# TempSensor.net
KiCad netlist of a schematic drawn in Altium Designer
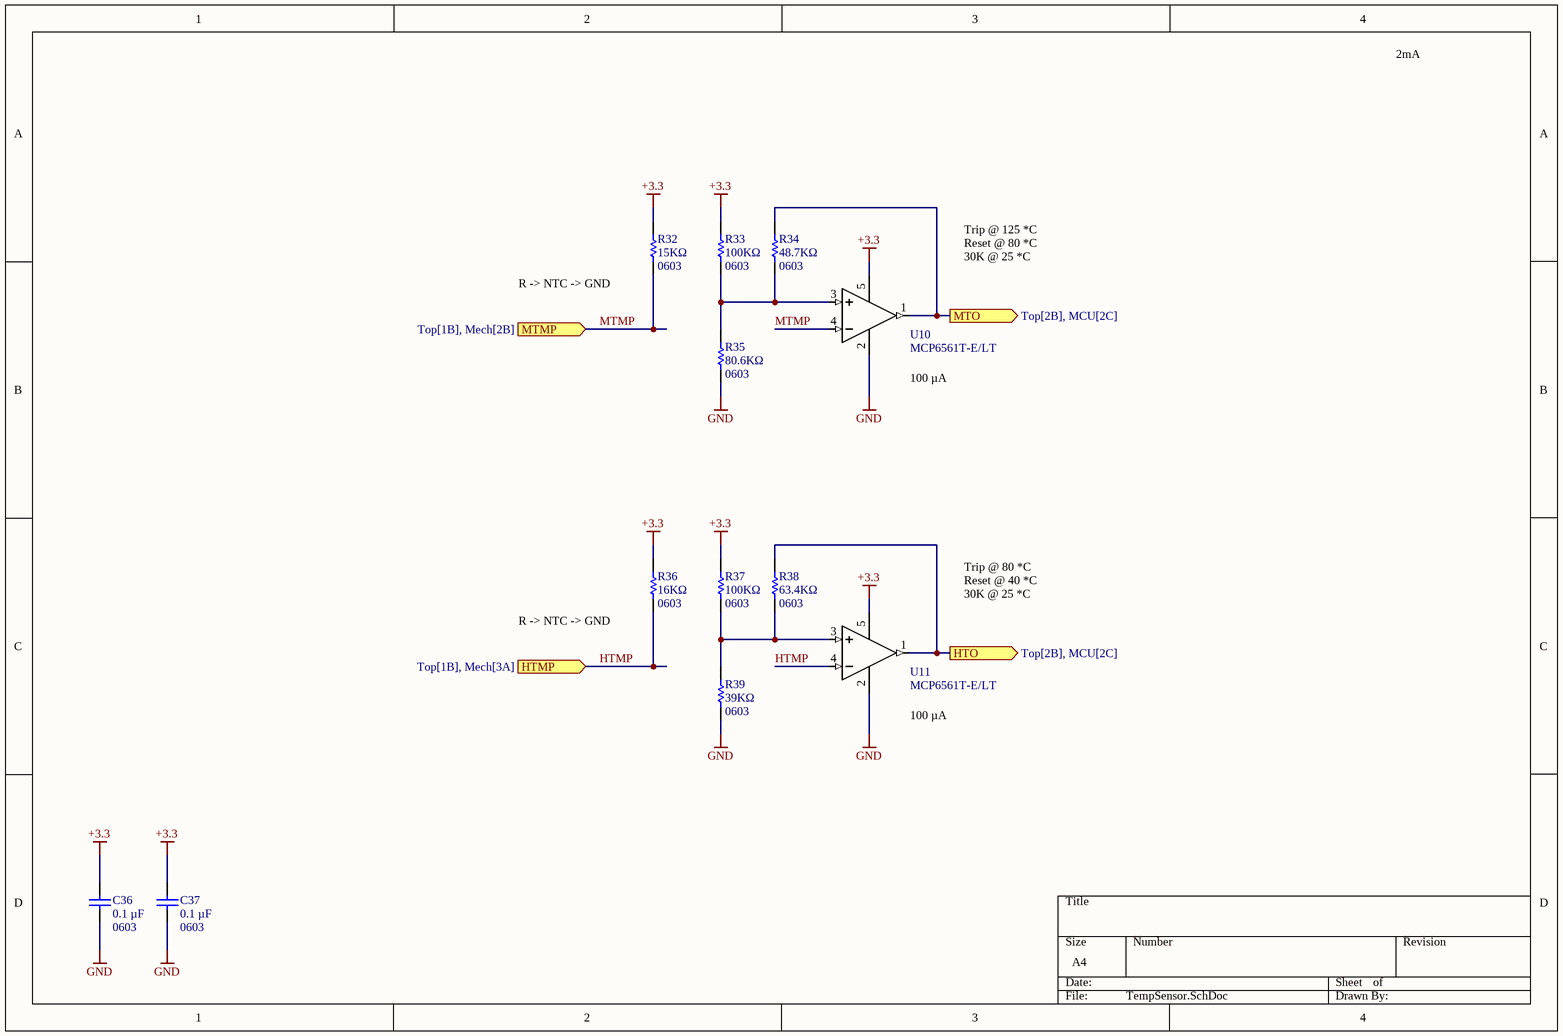
[diagram p0: TempSensor.SchDoc]

(export (version "E")
  (design (tool "Eeschema 10.0.6"))
  (components
    (comp (ref "C36")
      (value "0.1 µF")
      (footprint "0603")
      (description "0.1 µF ±20% 100V Ceramic Capacitor X7R 0603 (1608 Metric)")
      (fields (field (name "CASE") "0603") (field (name "TOLERANCE") "±20%") (field (name "VOLTAGE") "100V"))
      (libsource (lib "Murata Electronics") (part "GRM188R72A104MA35J"))
    )
    (comp (ref "C37")
      (value "0.1 µF")
      (footprint "0603")
      (description "0.1 µF ±20% 100V Ceramic Capacitor X7R 0603 (1608 Metric)")
      (fields (field (name "CASE") "0603") (field (name "TOLERANCE") "±20%") (field (name "VOLTAGE") "100V"))
      (libsource (lib "Murata Electronics") (part "GRM188R72A104MA35J"))
    )
    (comp (ref "R32")
      (value "15KΩ")
      (footprint "0603")
      (description "15 kOhms ±1% 0.1W, 1/10W Chip Resistor 0603 (1608 Metric) Automotive AEC-Q200 Thick Film")
      (fields (field (name "CASE") "0603") (field (name "TOLERANCE") "1%") (field (name "POWER") "0.1W"))
      (libsource (lib "Stackpole Electronics Inc") (part "RMCF0603FG15K0"))
    )
    (comp (ref "R33")
      (value "100KΩ")
      (footprint "0603")
      (description "100 kOhms ±1% 0.1W, 1/10W Chip Resistor 0603 (1608 Metric) Automotive AEC-Q200 Thick Film")
      (fields (field (name "CASE") "0603") (field (name "TOLERANCE") "1%") (field (name "POWER") "0.1W"))
      (libsource (lib "Stackpole Electronics Inc") (part "RMCF0603FG100K"))
    )
    (comp (ref "R34")
      (value "48.7KΩ")
      (footprint "0603")
      (description "48.7 kOhms ±1% 0.1W, 1/10W Chip Resistor 0603 (1608 Metric) Automotive AEC-Q200 Thick Film")
      (fields (field (name "CASE") "0603") (field (name "TOLERANCE") "1%") (field (name "POWER") "0.1W"))
      (libsource (lib "Stackpole Electronics Inc") (part "RMCF0603FT48K7"))
    )
    (comp (ref "R35")
      (value "80.6KΩ")
      (footprint "0603")
      (description "80.6 kOhms ±1% 0.1W, 1/10W Chip Resistor 0603 (1608 Metric) Automotive AEC-Q200 Thick Film")
      (fields (field (name "CASE") "0603") (field (name "TOLERANCE") "1%") (field (name "POWER") "0.1W"))
      (libsource (lib "Stackpole Electronics Inc") (part "RMCF0603FT80K6"))
    )
    (comp (ref "R36")
      (value "16KΩ")
      (footprint "0603")
      (description "16 kOhms ±1% 0.1W, 1/10W Chip Resistor 0603 (1608 Metric) Automotive AEC-Q200 Thick Film")
      (fields (field (name "CASE") "0603") (field (name "TOLERANCE") "1%") (field (name "POWER") "0.1W"))
      (libsource (lib "Stackpole Electronics Inc") (part "RMCF0603FG16K0"))
    )
    (comp (ref "R37")
      (value "100KΩ")
      (footprint "0603")
      (description "100 kOhms ±1% 0.1W, 1/10W Chip Resistor 0603 (1608 Metric) Automotive AEC-Q200 Thick Film")
      (fields (field (name "CASE") "0603") (field (name "TOLERANCE") "1%") (field (name "POWER") "0.1W"))
      (libsource (lib "Stackpole Electronics Inc") (part "RMCF0603FG100K"))
    )
    (comp (ref "R38")
      (value "63.4KΩ")
      (footprint "0603")
      (description "63.4 kOhms ±1% 0.1W, 1/10W Chip Resistor 0603 (1608 Metric) Automotive AEC-Q200 Thick Film")
      (fields (field (name "CASE") "0603") (field (name "TOLERANCE") "1%") (field (name "POWER") "0.1W"))
      (libsource (lib "Stackpole Electronics Inc") (part "RMCF0603FT63K4"))
    )
    (comp (ref "R39")
      (value "39KΩ")
      (footprint "0603")
      (description "39 kOhms ±1% 0.1W, 1/10W Chip Resistor 0603 (1608 Metric) Automotive AEC-Q200 Thick Film")
      (fields (field (name "CASE") "0603") (field (name "TOLERANCE") "1%") (field (name "POWER") "0.1W"))
      (libsource (lib "Stackpole Electronics Inc") (part "RMCF0603FG39K0"))
    )
    (comp (ref "U10")
      (value "MCP6561T-E/LT")
      (footprint "SC-70-5")
      (description "Comparator General Purpose CMOS, Push-Pull, Rail-to-Rail, TTL SC-70-5")
      (libsource (lib "Microchip Technology") (part "MCP6561T-E/LT"))
    )
    (comp (ref "U11")
      (value "MCP6561T-E/LT")
      (footprint "SC-70-5")
      (description "Comparator General Purpose CMOS, Push-Pull, Rail-to-Rail, TTL SC-70-5")
      (libsource (lib "Microchip Technology") (part "MCP6561T-E/LT"))
    )
  )
  (nets
    (net (code "1") (name "+3.3") (class "Default")
      (node (ref "C36") (pin "1") (pinfunction "1_1") (pintype "passive"))
      (node (ref "C37") (pin "1") (pinfunction "1_1") (pintype "passive"))
      (node (ref "R32") (pin "2") (pinfunction "2_2") (pintype "passive"))
      (node (ref "R33") (pin "2") (pinfunction "2_2") (pintype "passive"))
      (node (ref "R36") (pin "2") (pinfunction "2_2") (pintype "passive"))
      (node (ref "R37") (pin "2") (pinfunction "2_2") (pintype "passive"))
      (node (ref "U10") (pin "5") (pinfunction "V+_5") (pintype "power_in"))
      (node (ref "U11") (pin "5") (pinfunction "V+_5") (pintype "power_in"))
    )
    (net (code "2") (name "/HTMP") (class "Default")
      (node (ref "R36") (pin "1") (pinfunction "1_1") (pintype "passive"))
      (node (ref "U11") (pin "4") (pinfunction "-IN_4") (pintype "input"))
    )
    (net (code "3") (name "/HTO") (class "Default")
      (node (ref "R38") (pin "2") (pinfunction "2_2") (pintype "passive"))
      (node (ref "U11") (pin "1") (pinfunction "OUT_1") (pintype "output"))
    )
    (net (code "4") (name "/MTMP") (class "Default")
      (node (ref "R32") (pin "1") (pinfunction "1_1") (pintype "passive"))
      (node (ref "U10") (pin "4") (pinfunction "-IN_4") (pintype "input"))
    )
    (net (code "5") (name "/MTO") (class "Default")
      (node (ref "R34") (pin "2") (pinfunction "2_2") (pintype "passive"))
      (node (ref "U10") (pin "1") (pinfunction "OUT_1") (pintype "output"))
    )
    (net (code "6") (name "GND") (class "Default")
      (node (ref "C36") (pin "2") (pinfunction "2_2") (pintype "passive"))
      (node (ref "C37") (pin "2") (pinfunction "2_2") (pintype "passive"))
      (node (ref "R35") (pin "1") (pinfunction "1_1") (pintype "passive"))
      (node (ref "R39") (pin "1") (pinfunction "1_1") (pintype "passive"))
      (node (ref "U10") (pin "2") (pinfunction "V-_2") (pintype "power_in"))
      (node (ref "U11") (pin "2") (pinfunction "V-_2") (pintype "power_in"))
    )
    (net (code "7") (name "Net-(U10-+IN)") (class "Default")
      (node (ref "R33") (pin "1") (pinfunction "1_1") (pintype "passive"))
      (node (ref "R34") (pin "1") (pinfunction "1_1") (pintype "passive"))
      (node (ref "R35") (pin "2") (pinfunction "2_2") (pintype "passive"))
      (node (ref "U10") (pin "3") (pinfunction "+IN_3") (pintype "input"))
    )
    (net (code "8") (name "Net-(U11-+IN)") (class "Default")
      (node (ref "R37") (pin "1") (pinfunction "1_1") (pintype "passive"))
      (node (ref "R38") (pin "1") (pinfunction "1_1") (pintype "passive"))
      (node (ref "R39") (pin "2") (pinfunction "2_2") (pintype "passive"))
      (node (ref "U11") (pin "3") (pinfunction "+IN_3") (pintype "input"))
    )
  )
)
